# remora-2-power.net
KiCad netlist of a schematic drawn in Altium Designer
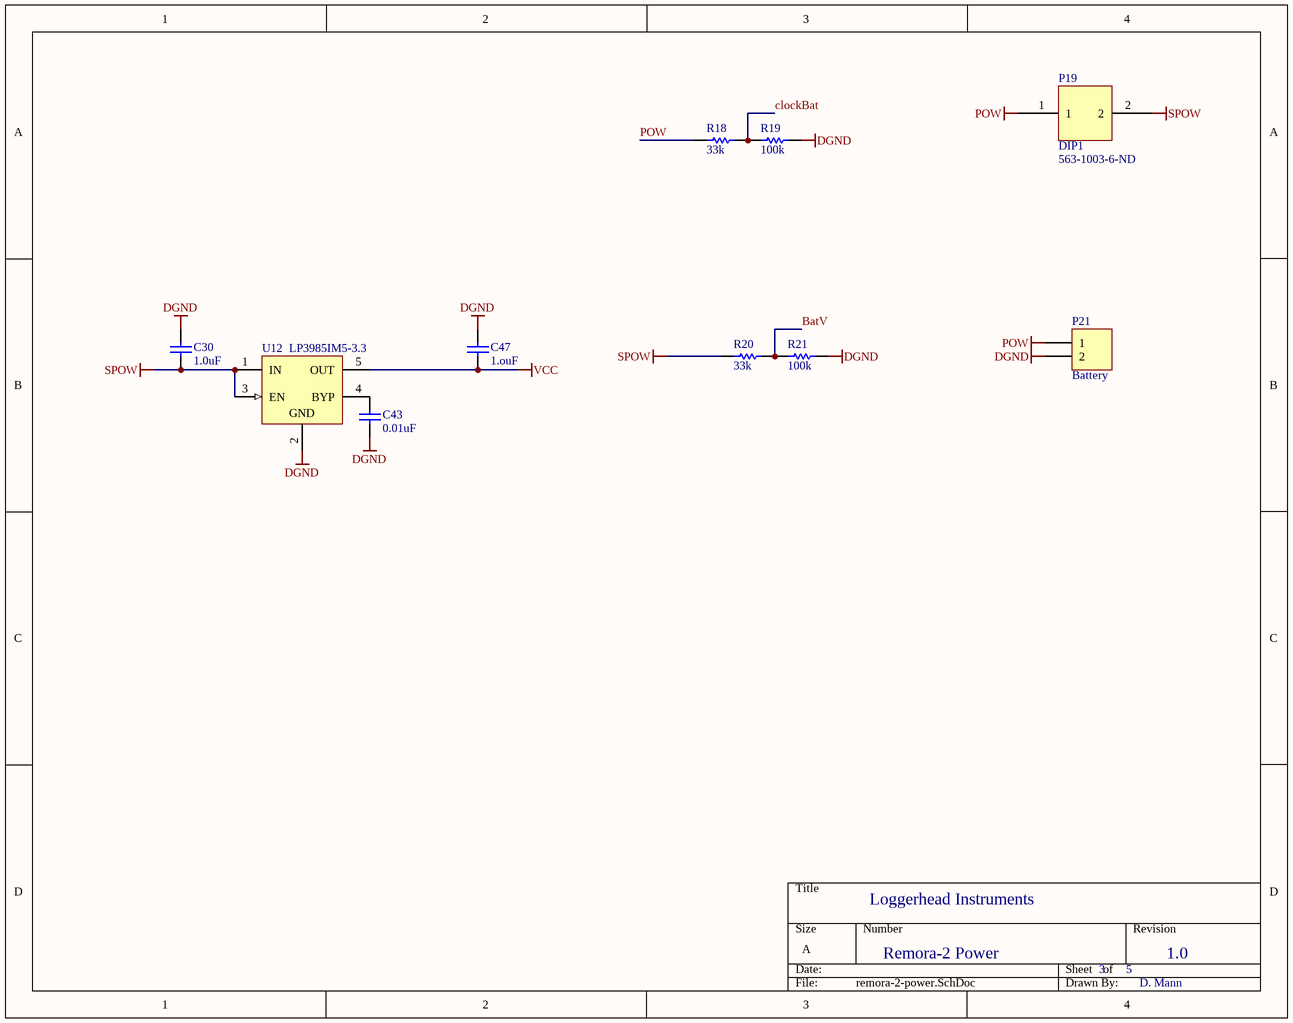
[diagram p0: remora-2-power.SchDoc]

(export (version "E")
  (design (tool "Eeschema 10.0.6"))
  (components
    (comp (ref "C30")
      (value "1.0uF")
      (footprint "0402")
      (description "Ceramic Chip Capacitor - Standard")
      (fields (field (name "PUBLISHER") "Altium Limited"))
      (libsource (lib "KEMET Chip Capacitor") (part "C0402"))
    )
    (comp (ref "C43")
      (value "0.01uF")
      (footprint "0402")
      (description "Ceramic Chip Capacitor - Standard")
      (fields (field (name "PUBLISHER") "Altium Limited"))
      (libsource (lib "KEMET Chip Capacitor") (part "C0402"))
    )
    (comp (ref "C47")
      (value "1.ouF")
      (footprint "0402")
      (description "Ceramic Chip Capacitor - Standard")
      (fields (field (name "PUBLISHER") "Altium Limited"))
      (libsource (lib "KEMET Chip Capacitor") (part "C0402"))
    )
    (comp (ref "P19")
      (value "DIP1")
      (footprint "DIP1")
      (fields (field (name "SUPPLIER PART NUMBER 1") "563-1003-6-ND"))
      (libsource (lib "Loggerhead") (part "DIP1"))
    )
    (comp (ref "P21")
      (value "Battery")
      (footprint "HDR1X2")
      (description "Header, 2-Pin")
      (fields (field (name "PUBLISHER") "Altium Limited"))
      (libsource (lib "Miscellaneous Connectors") (part "Header 2"))
    )
    (comp (ref "R18")
      (value "33k")
      (footprint "3-0603")
      (fields (field (name "PUBLISHER") "Altium Limited"))
      (libsource (lib "Panasonic Resistor") (part "ERJ3RK"))
    )
    (comp (ref "R19")
      (value "100k")
      (footprint "3-0603")
      (fields (field (name "PUBLISHER") "Altium Limited"))
      (libsource (lib "Panasonic Resistor") (part "ERJ3RK"))
    )
    (comp (ref "R20")
      (value "33k")
      (footprint "3-0603")
      (fields (field (name "PUBLISHER") "Altium Limited"))
      (libsource (lib "Panasonic Resistor") (part "ERJ3RK"))
    )
    (comp (ref "R21")
      (value "100k")
      (footprint "3-0603")
      (fields (field (name "PUBLISHER") "Altium Limited"))
      (libsource (lib "Panasonic Resistor") (part "ERJ3RK"))
    )
    (comp (ref "U12")
      (value "LP3985IM5-3.3")
      (footprint "MF05A_N")
      (description "Micropower, 150mA Low-Noise Ultra Low-Dropout CMOS Voltage Regulator")
      (fields
        (field (name "MANUFACTURER") "National Semiconductor")
        (field (name "DIGIKEYPARTNUMBER") "LP3985IM5-3.3CT-ND")
        (field (name "PUBLISHER") "Altium Limited")
      )
      (libsource (lib "NSC LDO") (part "LP3985IM5-3.3"))
    )
  )
  (nets
    (net (code "1") (name "/BatV") (class "Default")
      (node (ref "R20") (pin "1") (pinfunction "1_1") (pintype "passive"))
      (node (ref "R21") (pin "2") (pinfunction "2_2") (pintype "passive"))
    )
    (net (code "2") (name "/clockBat") (class "Default")
      (node (ref "R18") (pin "1") (pinfunction "1_1") (pintype "passive"))
      (node (ref "R19") (pin "2") (pinfunction "2_2") (pintype "passive"))
    )
    (net (code "3") (name "DGND") (class "Default")
      (node (ref "C30") (pin "2") (pinfunction "2_2") (pintype "passive"))
      (node (ref "C43") (pin "1") (pinfunction "1_1") (pintype "passive"))
      (node (ref "C47") (pin "2") (pinfunction "2_2") (pintype "passive"))
      (node (ref "P21") (pin "2") (pinfunction "2_2") (pintype "passive"))
      (node (ref "R19") (pin "1") (pinfunction "1_1") (pintype "passive"))
      (node (ref "R21") (pin "1") (pinfunction "1_1") (pintype "passive"))
      (node (ref "U12") (pin "2") (pinfunction "GND_2") (pintype "power_in"))
    )
    (net (code "4") (name "Net-(U12-BYP)") (class "Default")
      (node (ref "C43") (pin "2") (pinfunction "2_2") (pintype "passive"))
      (node (ref "U12") (pin "4") (pinfunction "BYP_4") (pintype "passive"))
    )
    (net (code "5") (name "POW") (class "Default")
      (node (ref "P19") (pin "1") (pinfunction "1_1") (pintype "passive"))
      (node (ref "P21") (pin "1") (pinfunction "1_1") (pintype "passive"))
      (node (ref "R18") (pin "2") (pinfunction "2_2") (pintype "passive"))
    )
    (net (code "6") (name "SPOW") (class "Default")
      (node (ref "C30") (pin "1") (pinfunction "1_1") (pintype "passive"))
      (node (ref "P19") (pin "2") (pinfunction "2_2") (pintype "passive"))
      (node (ref "R20") (pin "2") (pinfunction "2_2") (pintype "passive"))
      (node (ref "U12") (pin "1") (pinfunction "IN_1") (pintype "power_in"))
      (node (ref "U12") (pin "3") (pinfunction "EN_3") (pintype "input"))
    )
    (net (code "7") (name "VCC") (class "Default")
      (node (ref "C47") (pin "1") (pinfunction "1_1") (pintype "passive"))
      (node (ref "U12") (pin "5") (pinfunction "OUT_5") (pintype "power_in"))
    )
  )
)
